# food_box_board.net
KiCad netlist of a schematic drawn in Altium Designer
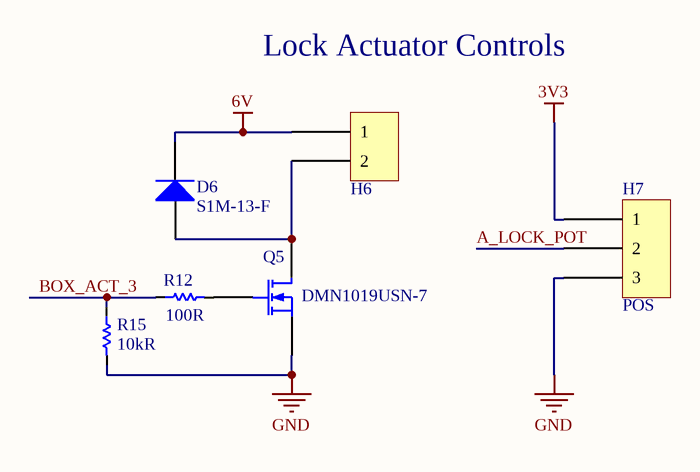
[diagram p0: food_box_board.SchDoc]

(export (version "E")
  (design (tool "Eeschema 10.0.6"))
  (components
    (comp (ref "D6")
      (value "S1M-13-F")
      (footprint "SMA")
      (description "Default Diode")
      (libsource (lib "Miscellaneous Devices") (part "Diode"))
    )
    (comp (ref "H6")
      (value "MOLEX_43650_2")
      (footprint "MOLEX_43650_2")
      (fields (field (name "MANUFACTURER") "Molex") (field (name "MANUFACTURER PART NUMBER") "43650-0227"))
      (libsource (lib "food_box") (part "MOLEX_43650_2"))
    )
    (comp (ref "H7")
      (value "POS")
      (footprint "MOLEX_43650_3")
      (description "Stepper position potentiometer")
      (libsource (lib "food_box") (part "TERM_3P"))
    )
    (comp (ref "Q5")
      (value "MOSFET-N")
      (footprint "SOT23-3")
      (description "MOSFET 12V N-Ch Enh FET 2426pF 27.3nC")
      (fields (field (name "MANUFACTURER") "Diodes") (field (name "MANUFACTURER PART NUMBER") "DMN1019USN-7"))
      (libsource (lib "Miscellaneous Devices") (part "MOSFET-N"))
    )
    (comp (ref "R12")
      (value "value")
      (footprint "RES 0603 L")
      (description "CRGCQ 0603 100R 5%")
      (fields
        (field (name "MANUFACTURER") "TE Connectivity")
        (field (name "MANUFACTURER PART NUMBER") "CRGCQ0603J100R")
        (field (name "RESISTANCE") "100R")
      )
      (libsource (lib "streetbot") (part "RES 0603"))
    )
    (comp (ref "R15")
      (value "value")
      (footprint "RES 0603 L")
      (description "TE CONNECTIVITY - CRGCQ0603J10K - RES, 10K, 5%, 0603, THICK FILM")
      (fields
        (field (name "MANUFACTURER") "TE Connectivity")
        (field (name "MANUFACTURER PART NUMBER") "CRGCQ0603J10K")
        (field (name "RESISTANCE") "10kR")
      )
      (libsource (lib "streetbot") (part "RES 0603"))
    )
  )
  (nets
    (net (code "1") (name "/A_LOCK_POT") (class "Default")
      (node (ref "H7") (pin "2") (pinfunction "2_2") (pintype "passive"))
    )
    (net (code "2") (name "/BOX_ACT_3") (class "Default")
      (node (ref "R12") (pin "2") (pinfunction "2_2") (pintype "passive"))
      (node (ref "R15") (pin "2") (pinfunction "2_2") (pintype "passive"))
    )
    (net (code "3") (name "3V3") (class "Default")
      (node (ref "H7") (pin "1") (pinfunction "1_1") (pintype "passive"))
    )
    (net (code "4") (name "6V") (class "Default")
      (node (ref "D6") (pin "2") (pinfunction "K_2") (pintype "passive"))
      (node (ref "H6") (pin "1") (pinfunction "1_1") (pintype "passive"))
    )
    (net (code "5") (name "GND") (class "Default")
      (node (ref "H7") (pin "3") (pinfunction "3_3") (pintype "passive"))
      (node (ref "Q5") (pin "3") (pinfunction "S_3") (pintype "passive"))
      (node (ref "R15") (pin "1") (pinfunction "1_1") (pintype "passive"))
    )
    (net (code "6") (name "Net-(D6-A)") (class "Default")
      (node (ref "D6") (pin "1") (pinfunction "A_1") (pintype "passive"))
      (node (ref "H6") (pin "2") (pinfunction "2_2") (pintype "passive"))
      (node (ref "Q5") (pin "1") (pinfunction "D_1") (pintype "passive"))
    )
    (net (code "7") (name "Net-(Q5-G)") (class "Default")
      (node (ref "Q5") (pin "2") (pinfunction "G_2") (pintype "passive"))
      (node (ref "R12") (pin "1") (pinfunction "1_1") (pintype "passive"))
    )
  )
)
